# main.net
KiCad netlist of a schematic drawn in EAGLE
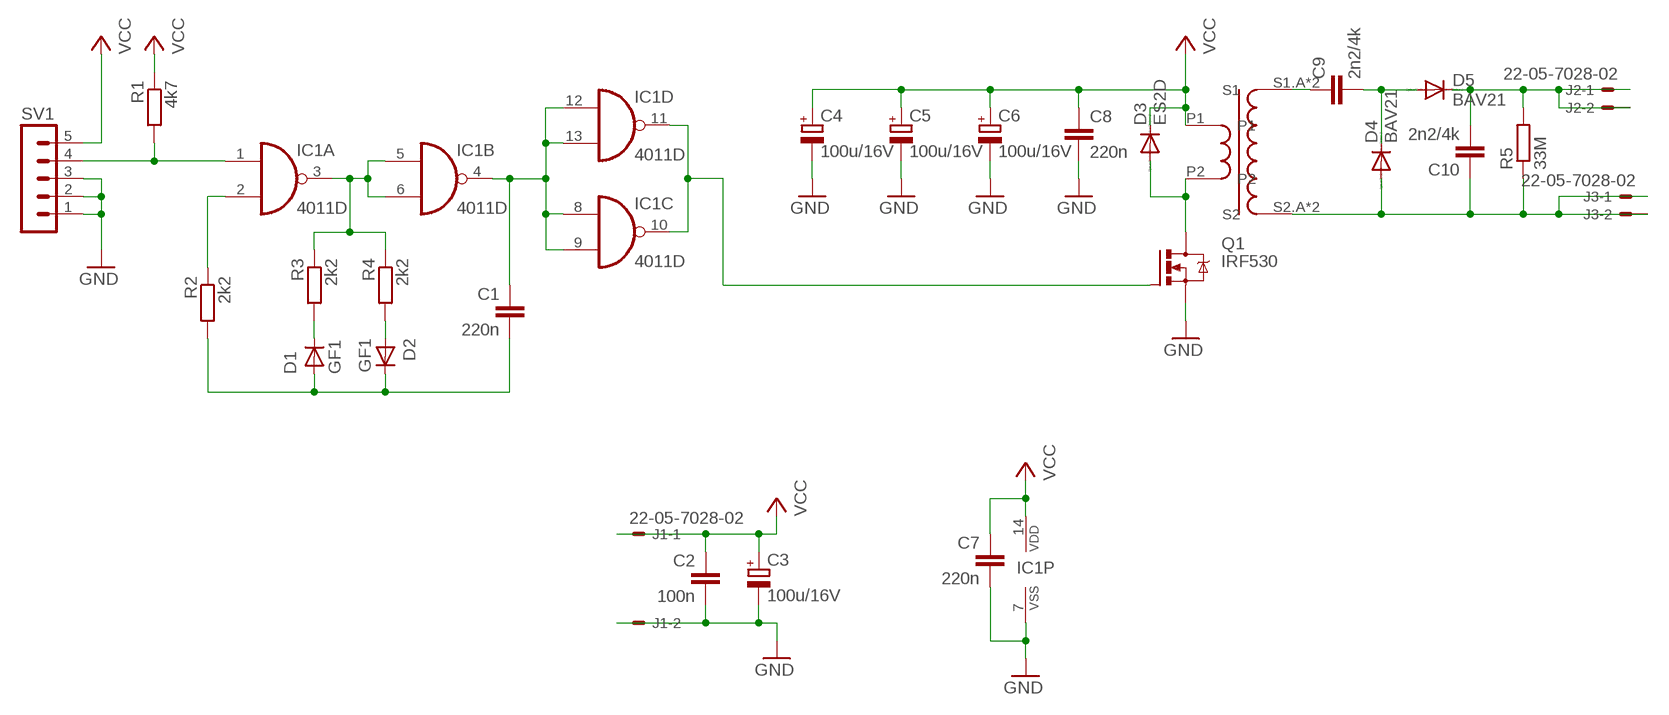
[diagram p0: schematic, sheet 1]

(export (version "E")
  (design (tool "Eeschema 10.0.6"))
  (components
    (comp (ref "11")
      (value "CCFL_INVERTER_COIL")
      (footprint "eagle-import:CCFL_INVERTER_COIL")
      (libsource (lib "eagle-import") (part "CCFL_INVERTER_COIL"))
    )
    (comp (ref "C1")
      (value "220n")
      (footprint "eagle-import:C025-025X050")
      (libsource (lib "eagle-import") (part "resistor_C-EU025-025X050"))
    )
    (comp (ref "C2")
      (value "100n")
      (footprint "eagle-import:C0805")
      (libsource (lib "eagle-import") (part "resistor_C-EUC0805"))
    )
    (comp (ref "C3")
      (value "100u/16V")
      (footprint "eagle-import:153CLV-0505")
      (libsource (lib "eagle-import") (part "CPOL-EU153CLV-0505"))
    )
    (comp (ref "C4")
      (value "100u/16V")
      (footprint "eagle-import:153CLV-0505")
      (libsource (lib "eagle-import") (part "CPOL-EU153CLV-0505"))
    )
    (comp (ref "C5")
      (value "100u/16V")
      (footprint "eagle-import:153CLV-0505")
      (libsource (lib "eagle-import") (part "resistor_CPOL-EU153CLV-0505"))
    )
    (comp (ref "C6")
      (value "100u/16V")
      (footprint "eagle-import:153CLV-0505")
      (libsource (lib "eagle-import") (part "CPOL-EU153CLV-0505"))
    )
    (comp (ref "C7")
      (value "220n")
      (footprint "eagle-import:C0805")
      (libsource (lib "eagle-import") (part "resistor_C-EUC0805"))
    )
    (comp (ref "C8")
      (value "220n")
      (footprint "eagle-import:C0805")
      (libsource (lib "eagle-import") (part "resistor_C-EUC0805"))
    )
    (comp (ref "C9")
      (value "2n2/4k")
      (footprint "eagle-import:C075-042X103")
      (libsource (lib "eagle-import") (part "C-EU075-042X103"))
    )
    (comp (ref "C10")
      (value "2n2/4k")
      (footprint "eagle-import:C075-042X103")
      (libsource (lib "eagle-import") (part "resistor_C-EU075-042X103"))
    )
    (comp (ref "D1")
      (value "GF1")
      (footprint "eagle-import:SMA-DO214AC")
      (libsource (lib "eagle-import") (part "GF1"))
    )
    (comp (ref "D2")
      (value "GF1")
      (footprint "eagle-import:SMA-DO214AC")
      (libsource (lib "eagle-import") (part "GF1"))
    )
    (comp (ref "D3")
      (value "ES2D")
      (footprint "eagle-import:SMB")
      (libsource (lib "eagle-import") (part "ES2D"))
    )
    (comp (ref "D4")
      (value "BAV21")
      (footprint "eagle-import:DO35-10")
      (libsource (lib "eagle-import") (part "BAV21"))
    )
    (comp (ref "D5")
      (value "BAV21")
      (footprint "eagle-import:DO35-10")
      (libsource (lib "eagle-import") (part "BAV21"))
    )
    (comp (ref "IC1")
      (value "4011D")
      (footprint "eagle-import:SO14")
      (libsource (lib "eagle-import") (part "4011D"))
    )
    (comp (ref "J1")
      (value "22-05-7028-02")
      (footprint "eagle-import:7395-02")
      (libsource (lib "eagle-import") (part "22-?-0205-7028"))
    )
    (comp (ref "J2")
      (value "22-05-7028-02")
      (footprint "eagle-import:7395-02")
      (libsource (lib "eagle-import") (part "22-?-0205-7028"))
    )
    (comp (ref "J3")
      (value "22-05-7028-02")
      (footprint "eagle-import:7395-02")
      (libsource (lib "eagle-import") (part "22-?-0205-7028"))
    )
    (comp (ref "Q1")
      (value "IRF530")
      (footprint "eagle-import:TO220BV")
      (libsource (lib "eagle-import") (part "IRF530"))
    )
    (comp (ref "R1")
      (value "4k7")
      (footprint "eagle-import:M0805")
      (libsource (lib "eagle-import") (part "R-EU_M0805"))
    )
    (comp (ref "R2")
      (value "2k2")
      (footprint "eagle-import:M0805")
      (libsource (lib "eagle-import") (part "R-EU_M0805"))
    )
    (comp (ref "R3")
      (value "2k2")
      (footprint "eagle-import:M0805")
      (libsource (lib "eagle-import") (part "R-EU_M0805"))
    )
    (comp (ref "R4")
      (value "2k2")
      (footprint "eagle-import:M0805")
      (libsource (lib "eagle-import") (part "R-EU_M0805"))
    )
    (comp (ref "R5")
      (value "33M")
      (footprint "eagle-import:0207_10")
      (libsource (lib "eagle-import") (part "R-EU_0207/10"))
    )
    (comp (ref "SV1")
      (value "MA05-1")
      (footprint "eagle-import:MA05-1")
      (libsource (lib "eagle-import") (part "MA05-1"))
    )
  )
  (nets
    (net (code "1") (name "GND") (class "Default")
      (node (ref "C2") (pin "2") (pinfunction "2_2") (pintype "passive"))
      (node (ref "C3") (pin "-") (pinfunction "-_-") (pintype "passive"))
      (node (ref "C4") (pin "-") (pinfunction "-_-") (pintype "passive"))
      (node (ref "C5") (pin "-") (pinfunction "-_-") (pintype "passive"))
      (node (ref "C6") (pin "-") (pinfunction "-_-") (pintype "passive"))
      (node (ref "C7") (pin "2") (pinfunction "2_2") (pintype "passive"))
      (node (ref "C8") (pin "2") (pinfunction "2_2") (pintype "passive"))
      (node (ref "IC1") (pin "7") (pinfunction "VSS_7") (pintype "power_in"))
      (node (ref "J1") (pin "2") (pinfunction "S_2") (pintype "passive"))
      (node (ref "Q1") (pin "S") (pinfunction "S_S") (pintype "passive"))
      (node (ref "SV1") (pin "1") (pinfunction "1_1") (pintype "passive"))
      (node (ref "SV1") (pin "2") (pinfunction "2_2") (pintype "passive"))
      (node (ref "SV1") (pin "3") (pinfunction "3_3") (pintype "passive"))
    )
    (net (code "2") (name "Net-(11-PadP2)") (class "Default")
      (node (ref "11") (pin "P2") (pinfunction "P2_P2") (pintype "input"))
      (node (ref "D3") (pin "A") (pinfunction "A_A") (pintype "passive"))
      (node (ref "Q1") (pin "D") (pinfunction "D_D") (pintype "passive"))
    )
    (net (code "3") (name "Net-(11-S1-PadS1.A)") (class "Default")
      (node (ref "11") (pin "S1.A") (pinfunction "S1_S1.A") (pintype "output"))
      (node (ref "11") (pin "S1.B") (pinfunction "S1_S1.B") (pintype "output"))
      (node (ref "C9") (pin "1") (pinfunction "1_1") (pintype "passive"))
    )
    (net (code "4") (name "Net-(C9-Pad2)") (class "Default")
      (node (ref "C9") (pin "2") (pinfunction "2_2") (pintype "passive"))
      (node (ref "D4") (pin "C") (pinfunction "C_C") (pintype "passive"))
      (node (ref "D5") (pin "A") (pinfunction "A_A") (pintype "passive"))
    )
    (net (code "5") (name "Net-(D1-C)") (class "Default")
      (node (ref "D1") (pin "K") (pinfunction "C_K") (pintype "passive"))
      (node (ref "R3") (pin "2") (pinfunction "2_2") (pintype "passive"))
    )
    (net (code "6") (name "Net-(D2-C)") (class "Default")
      (node (ref "C1") (pin "2") (pinfunction "2_2") (pintype "passive"))
      (node (ref "D1") (pin "A") (pinfunction "A_A") (pintype "passive"))
      (node (ref "D2") (pin "K") (pinfunction "C_K") (pintype "passive"))
      (node (ref "R2") (pin "2") (pinfunction "2_2") (pintype "passive"))
    )
    (net (code "7") (name "Net-(D2-PadA)") (class "Default")
      (node (ref "D2") (pin "A") (pinfunction "A_A") (pintype "passive"))
      (node (ref "R4") (pin "2") (pinfunction "2_2") (pintype "passive"))
    )
    (net (code "8") (name "Net-(IC1A-I0)") (class "Default")
      (node (ref "IC1") (pin "1") (pinfunction "I0_1") (pintype "input"))
      (node (ref "R1") (pin "2") (pinfunction "2_2") (pintype "passive"))
      (node (ref "SV1") (pin "4") (pinfunction "4_4") (pintype "passive"))
    )
    (net (code "9") (name "Net-(IC1A-I1)") (class "Default")
      (node (ref "IC1") (pin "2") (pinfunction "I1_2") (pintype "input"))
      (node (ref "R2") (pin "1") (pinfunction "1_1") (pintype "passive"))
    )
    (net (code "10") (name "Net-(IC1A-O)") (class "Default")
      (node (ref "IC1") (pin "3") (pinfunction "O_3") (pintype "output"))
      (node (ref "IC1") (pin "5") (pinfunction "I0_5") (pintype "input"))
      (node (ref "IC1") (pin "6") (pinfunction "I1_6") (pintype "input"))
      (node (ref "R3") (pin "1") (pinfunction "1_1") (pintype "passive"))
      (node (ref "R4") (pin "1") (pinfunction "1_1") (pintype "passive"))
    )
    (net (code "11") (name "Net-(IC1B-O)") (class "Default")
      (node (ref "C1") (pin "1") (pinfunction "1_1") (pintype "passive"))
      (node (ref "IC1") (pin "12") (pinfunction "I0_12") (pintype "input"))
      (node (ref "IC1") (pin "13") (pinfunction "I1_13") (pintype "input"))
      (node (ref "IC1") (pin "4") (pinfunction "O_4") (pintype "output"))
      (node (ref "IC1") (pin "8") (pinfunction "I0_8") (pintype "input"))
      (node (ref "IC1") (pin "9") (pinfunction "I1_9") (pintype "input"))
    )
    (net (code "12") (name "Net-(IC1C-O)") (class "Default")
      (node (ref "IC1") (pin "10") (pinfunction "O_10") (pintype "output"))
      (node (ref "IC1") (pin "11") (pinfunction "O_11") (pintype "output"))
      (node (ref "Q1") (pin "G") (pinfunction "G_G") (pintype "passive"))
    )
    (net (code "13") (name "Net-(J2A-S)") (class "Default")
      (node (ref "C10") (pin "2") (pinfunction "2_2") (pintype "passive"))
      (node (ref "D5") (pin "C") (pinfunction "C_C") (pintype "passive"))
      (node (ref "J2") (pin "1") (pinfunction "S_1") (pintype "passive"))
      (node (ref "J2") (pin "2") (pinfunction "S_2") (pintype "passive"))
      (node (ref "R5") (pin "2") (pinfunction "2_2") (pintype "passive"))
    )
    (net (code "14") (name "Net-(J3A-S)") (class "Default")
      (node (ref "11") (pin "S2.A") (pinfunction "S2_S2.A") (pintype "output"))
      (node (ref "11") (pin "S2.B") (pinfunction "S2_S2.B") (pintype "output"))
      (node (ref "C10") (pin "1") (pinfunction "1_1") (pintype "passive"))
      (node (ref "D4") (pin "A") (pinfunction "A_A") (pintype "passive"))
      (node (ref "J3") (pin "1") (pinfunction "S_1") (pintype "passive"))
      (node (ref "J3") (pin "2") (pinfunction "S_2") (pintype "passive"))
      (node (ref "R5") (pin "1") (pinfunction "1_1") (pintype "passive"))
    )
    (net (code "15") (name "VCC") (class "Default")
      (node (ref "11") (pin "P1") (pinfunction "P1_P1") (pintype "input"))
      (node (ref "C2") (pin "1") (pinfunction "1_1") (pintype "passive"))
      (node (ref "C3") (pin "+") (pinfunction "+_+") (pintype "passive"))
      (node (ref "C4") (pin "+") (pinfunction "+_+") (pintype "passive"))
      (node (ref "C5") (pin "+") (pinfunction "+_+") (pintype "passive"))
      (node (ref "C6") (pin "+") (pinfunction "+_+") (pintype "passive"))
      (node (ref "C7") (pin "1") (pinfunction "1_1") (pintype "passive"))
      (node (ref "C8") (pin "1") (pinfunction "1_1") (pintype "passive"))
      (node (ref "D3") (pin "C") (pinfunction "C_C") (pintype "passive"))
      (node (ref "IC1") (pin "14") (pinfunction "VDD_14") (pintype "power_in"))
      (node (ref "J1") (pin "1") (pinfunction "S_1") (pintype "passive"))
      (node (ref "R1") (pin "1") (pinfunction "1_1") (pintype "passive"))
      (node (ref "SV1") (pin "5") (pinfunction "5_5") (pintype "passive"))
    )
  )
)
